# obc-v2_FRAM-FLASH.net
KiCad netlist of a schematic drawn in Altium Designer
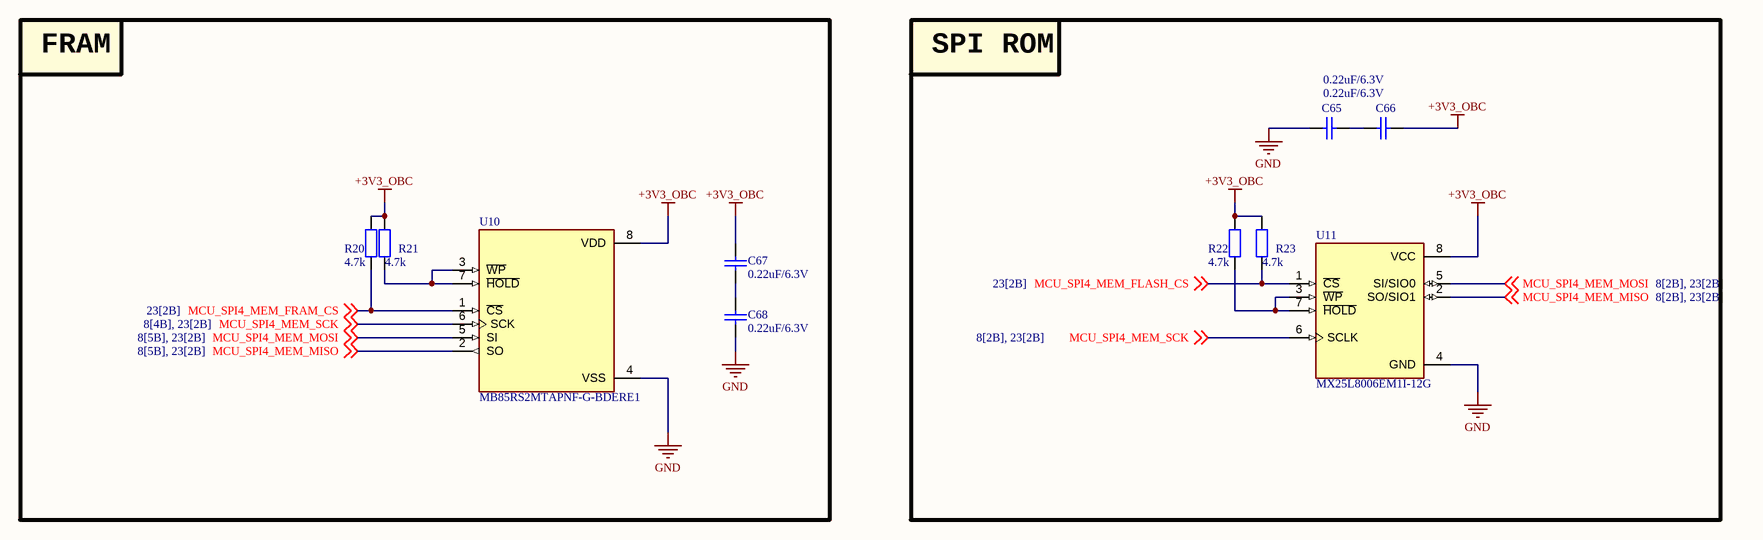
[diagram p0: obc-v2_FRAM-FLASH.SchDoc]

(export (version "E")
  (design (tool "Eeschema 10.0.6"))
  (components
    (comp (ref "C65")
      (value "0.22uF/6.3V")
      (footprint "CAP_C_1005X60")
      (description "CAPC")
      (libsource (lib "Altium_Lib_by_KhueNguyenCreator") (part "Tu 0402 33nF 10V"))
    )
    (comp (ref "C66")
      (value "0.22uF/6.3V")
      (footprint "CAP_C_1005X60")
      (description "CAPC")
      (libsource (lib "Altium_Lib_by_KhueNguyenCreator") (part "Tu 0402 33nF 10V"))
    )
    (comp (ref "C67")
      (value "0.22uF/6.3V")
      (footprint "CAP_C_1005X60")
      (description "CAPC")
      (libsource (lib "Altium_Lib_by_KhueNguyenCreator") (part "Tu 0402 33nF 10V"))
    )
    (comp (ref "C68")
      (value "0.22uF/6.3V")
      (footprint "CAP_C_1005X60")
      (description "CAPC")
      (libsource (lib "Altium_Lib_by_KhueNguyenCreator") (part "Tu 0402 33nF 10V"))
    )
    (comp (ref "R20")
      (value "4.7k")
      (footprint "RES_C_1608X60")
      (description "RES")
      (libsource (lib "Altium_Lib_by_KhueNguyenCreator") (part "Tro 0603 1% 10k"))
    )
    (comp (ref "R21")
      (value "4.7k")
      (footprint "RES_C_1608X60")
      (description "RES")
      (libsource (lib "Altium_Lib_by_KhueNguyenCreator") (part "Tro 0603 1% 10k"))
    )
    (comp (ref "R22")
      (value "4.7k")
      (footprint "RES_C_1608X60")
      (description "RES")
      (libsource (lib "Altium_Lib_by_KhueNguyenCreator") (part "Tro 0603 1% 10k"))
    )
    (comp (ref "R23")
      (value "4.7k")
      (footprint "RES_C_1608X60")
      (description "RES")
      (libsource (lib "Altium_Lib_by_KhueNguyenCreator") (part "Tro 0603 1% 10k"))
    )
    (comp (ref "U10")
      (value "MB85RS2MTAPNF-G-BDERE1")
      (footprint "SOIC127P602X173-8N")
      (description "FRAM _Ferroelectric RAM_ Memory IC 2Mb _256K x 8_ SPI 40MHz 8-SOP")
      (fields (field (name "MF") "Fujitsu Electronics") (field (name "DIGI-KEY_PART_NUMBER") "865-1286-1-ND"))
      (libsource (lib "MB85RS2MTAPNF-G-BDERE1") (part "MB85RS2MTAPNF-G-BDERE1"))
    )
    (comp (ref "U11")
      (value "MX25L8006EM1I-12G")
      (footprint "SOIC127P602X173-8N")
      (description "FLASH - NOR Memory IC 8Mb (1M x 8) SPI 86 MHz 8-SOP")
      (fields (field (name "MF") "Macronix"))
      (libsource (lib "MX25L8006EM1I-12G") (part "MX25L8006EM1I-12G"))
    )
  )
  (nets
    (net (code "1") (name "+3V3_OBC") (class "Default")
      (node (ref "C66") (pin "1") (pinfunction "1_1") (pintype "passive"))
      (node (ref "C67") (pin "1") (pinfunction "1_1") (pintype "passive"))
      (node (ref "R20") (pin "2") (pinfunction "2_2") (pintype "passive"))
      (node (ref "R21") (pin "2") (pinfunction "2_2") (pintype "passive"))
      (node (ref "R22") (pin "2") (pinfunction "2_2") (pintype "passive"))
      (node (ref "R23") (pin "2") (pinfunction "2_2") (pintype "passive"))
      (node (ref "U10") (pin "8") (pinfunction "VDD_8") (pintype "power_in"))
      (node (ref "U11") (pin "8") (pinfunction "VCC_8") (pintype "power_in"))
    )
    (net (code "2") (name "GND") (class "Default")
      (node (ref "C65") (pin "2") (pinfunction "2_2") (pintype "passive"))
      (node (ref "C68") (pin "1") (pinfunction "1_1") (pintype "passive"))
      (node (ref "U10") (pin "4") (pinfunction "VSS_4") (pintype "power_in"))
      (node (ref "U11") (pin "4") (pinfunction "GND_4") (pintype "power_in"))
    )
    (net (code "3") (name "MCU_SPI4_MEM_FLASH_CS") (class "Default")
      (node (ref "R23") (pin "1") (pinfunction "1_1") (pintype "passive"))
      (node (ref "U11") (pin "1") (pinfunction "~{CS}_1") (pintype "input"))
    )
    (net (code "4") (name "MCU_SPI4_MEM_FRAM_CS") (class "Default")
      (node (ref "R20") (pin "1") (pinfunction "1_1") (pintype "passive"))
      (node (ref "U10") (pin "1") (pinfunction "~{CS}_1") (pintype "input"))
    )
    (net (code "5") (name "MCU_SPI4_MEM_MISO") (class "Default")
      (node (ref "U10") (pin "2") (pinfunction "SO_2") (pintype "output"))
      (node (ref "U11") (pin "2") (pinfunction "SO/SIO1_2") (pintype "bidirectional"))
    )
    (net (code "6") (name "MCU_SPI4_MEM_MOSI") (class "Default")
      (node (ref "U10") (pin "5") (pinfunction "SI_5") (pintype "input"))
      (node (ref "U11") (pin "5") (pinfunction "SI/SIO0_5") (pintype "bidirectional"))
    )
    (net (code "7") (name "MCU_SPI4_MEM_SCK") (class "Default")
      (node (ref "U10") (pin "6") (pinfunction "SCK_6") (pintype "input"))
      (node (ref "U11") (pin "6") (pinfunction "SCLK_6") (pintype "input"))
    )
    (net (code "8") (name "Net-(C65-Pad1)") (class "Default")
      (node (ref "C65") (pin "1") (pinfunction "1_1") (pintype "passive"))
      (node (ref "C66") (pin "2") (pinfunction "2_2") (pintype "passive"))
    )
    (net (code "9") (name "Net-(C67-Pad2)") (class "Default")
      (node (ref "C67") (pin "2") (pinfunction "2_2") (pintype "passive"))
      (node (ref "C68") (pin "2") (pinfunction "2_2") (pintype "passive"))
    )
    (net (code "10") (name "Net-(U10-~{HOLD})") (class "Default")
      (node (ref "R21") (pin "1") (pinfunction "1_1") (pintype "passive"))
      (node (ref "U10") (pin "3") (pinfunction "~{WP}_3") (pintype "input"))
      (node (ref "U10") (pin "7") (pinfunction "~{HOLD}_7") (pintype "input"))
    )
    (net (code "11") (name "Net-(U11-~{HOLD})") (class "Default")
      (node (ref "R22") (pin "1") (pinfunction "1_1") (pintype "passive"))
      (node (ref "U11") (pin "3") (pinfunction "~{WP}_3") (pintype "input"))
      (node (ref "U11") (pin "7") (pinfunction "~{HOLD}_7") (pintype "input"))
    )
  )
)
